# 3_SCHEMATIC_new.net
KiCad netlist of a schematic drawn in Altium Designer
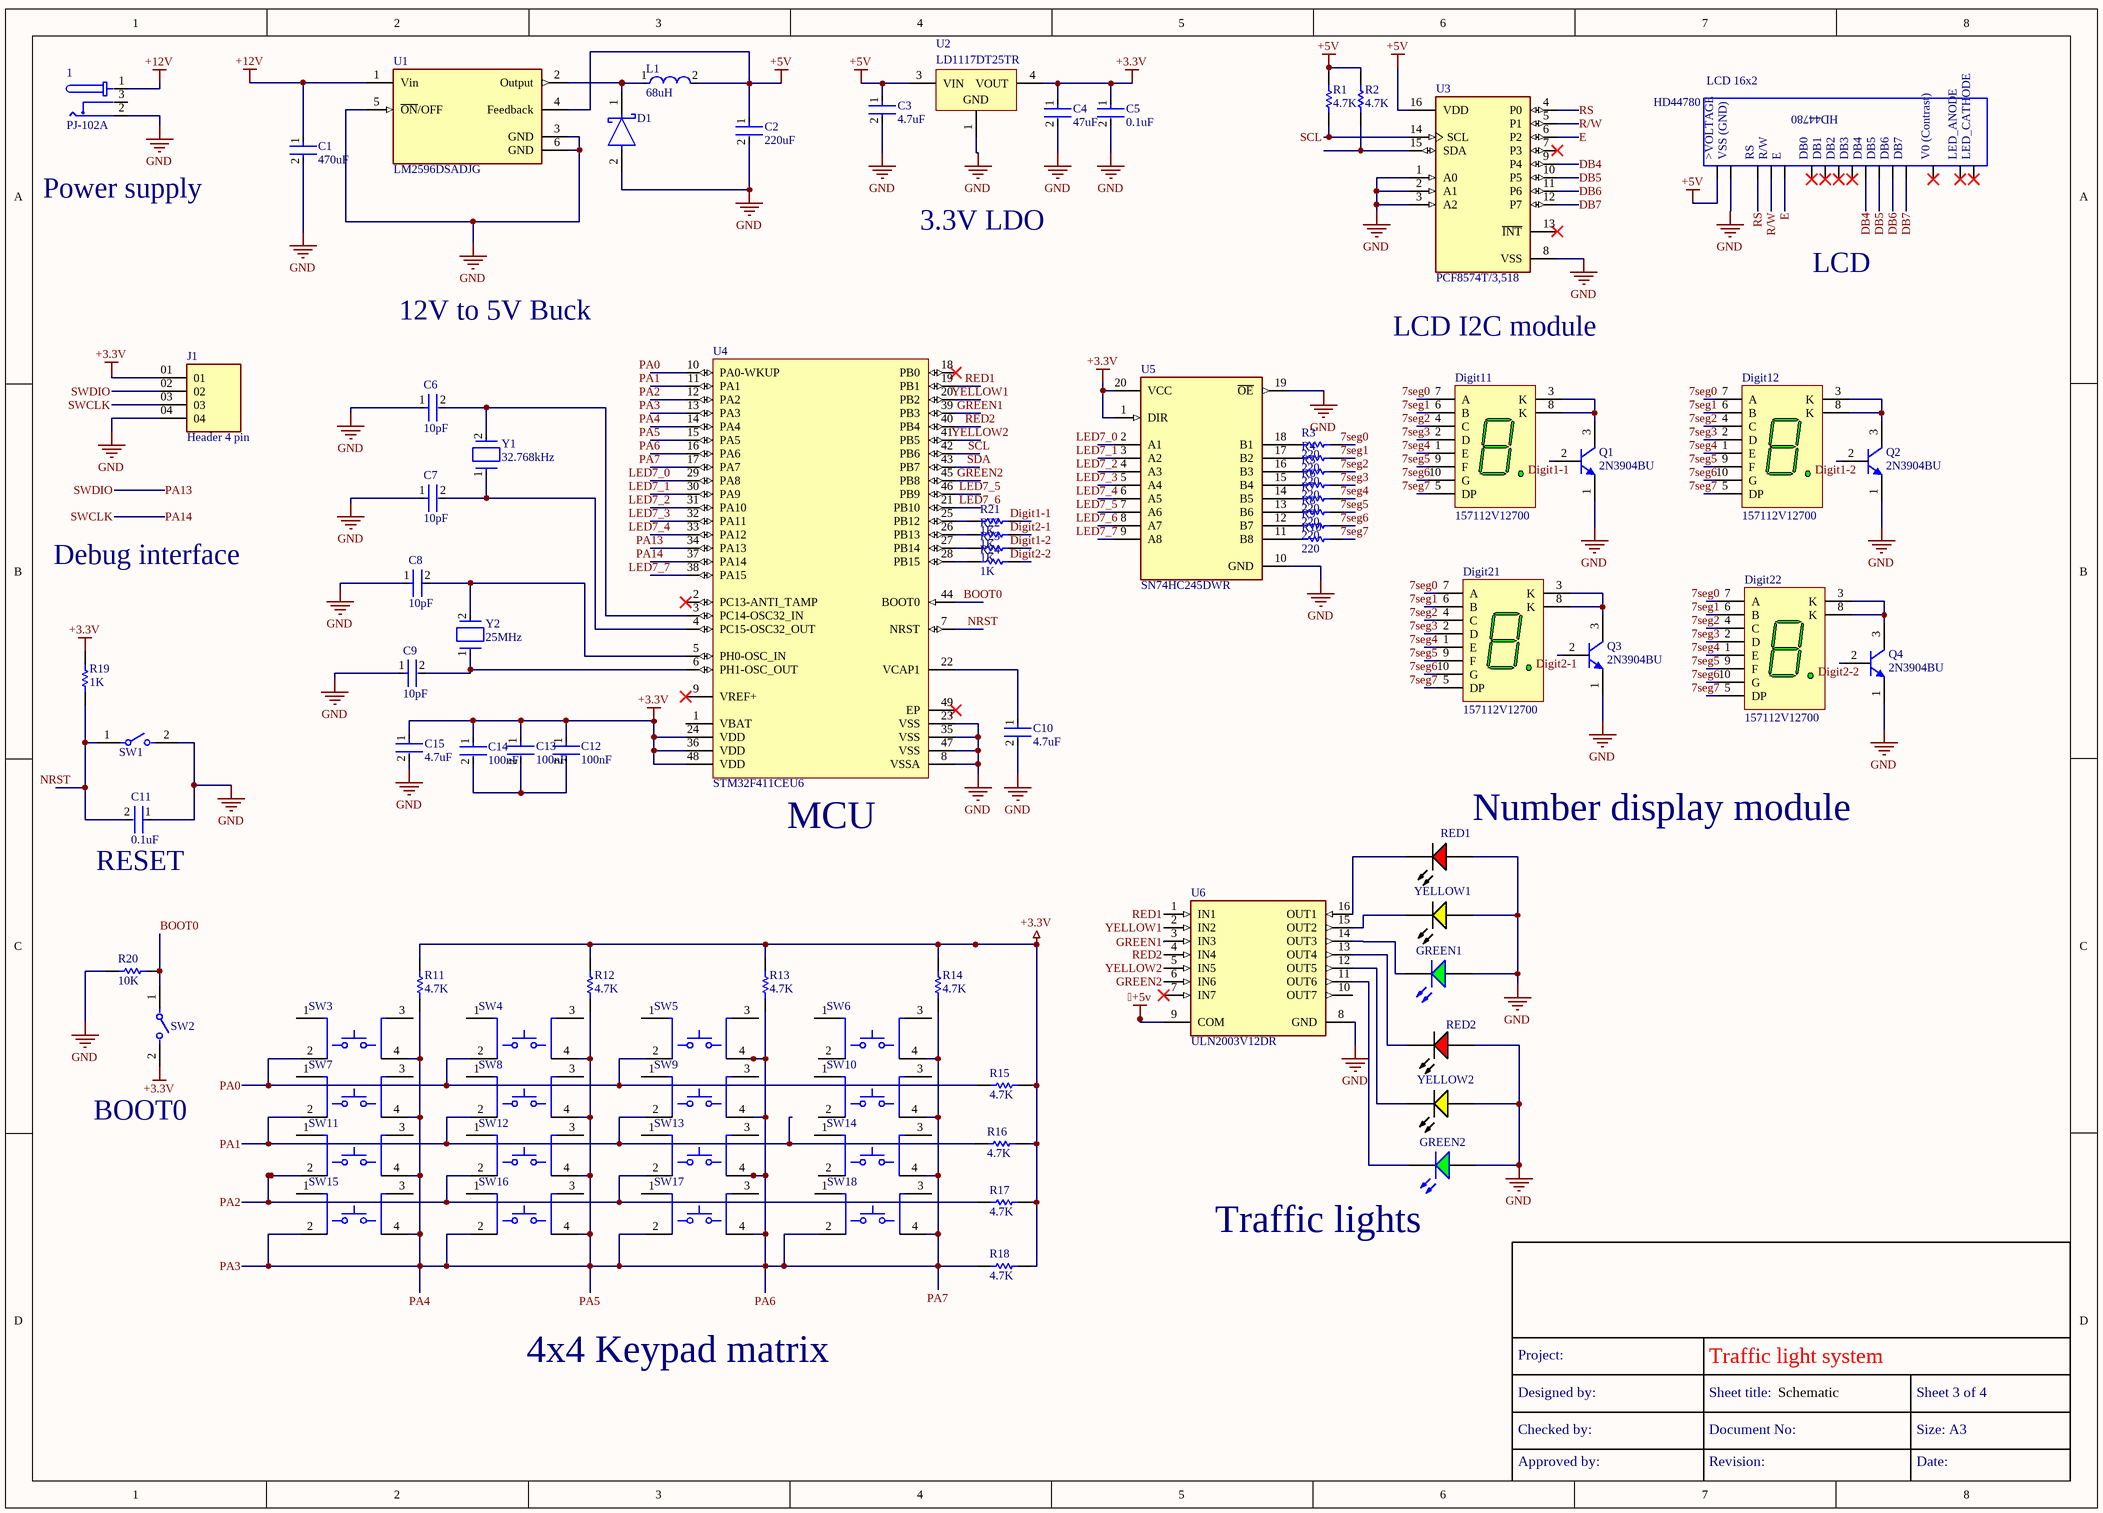
[diagram p0: [3] SCHEMATIC (new).SchDoc]

(export (version "E")
  (design (tool "Eeschema 10.0.6"))
  (components
    (comp (ref "1")
      (value "PJ-102A")
      (footprint "CUI_PJ-102A")
      (description "2.0 x 6.5 mm, 2.5 A, Horizontal, Through Hole, Tapered Pins, Dc Power Jack Connector")
      (fields (field (name "MF") "Same Sky"))
      (libsource (lib "PJ-102A") (part "PJ-102A"))
    )
    (comp (ref "C1")
      (value "470uF")
      (footprint "FP-1206-L_3_2_0_2-W_1_6_0-IPC_A")
      (description "None")
      (fields (field (name "TOLERANCE") "20%"))
      (libsource (lib "47uF capacitor") (part "CMP-14477-001040-2"))
    )
    (comp (ref "C2")
      (value "220uF")
      (footprint "FP-CC1210-GD-IPC_C")
      (description "CAP CER 220UF 6.3V X5R 1210")
      (fields (field (name "TOLERANCE") "20%"))
      (libsource (lib "220uF capacitor") (part "CMP-03422-001480-1"))
    )
    (comp (ref "C3")
      (value "4.7uF")
      (footprint "FP-1210-L_3_2_0_3-W_2_5_0-IPC_B")
      (description "None")
      (libsource (lib "4.7uF capacitor") (part "CMP-14477-002040-2"))
    )
    (comp (ref "C4")
      (value "47uF")
      (footprint "FP-1206-L_3_2_0_2-W_1_6_0-IPC_A")
      (description "None")
      (fields (field (name "TOLERANCE") "20%"))
      (libsource (lib "47uF capacitor") (part "CMP-14477-001040-2"))
    )
    (comp (ref "C5")
      (value "0.1uF")
      (footprint "FP-C1206C-EB-MFG")
      (description "C1206 0.10 μF U2J 2.00% 16 V")
      (fields
        (field (name "MANUFACTURER PART NUMBER") "C1206C104G4JACAUTO")
        (field (name "TOLERANCE") "0.02")
      )
      (libsource (lib "0.1uF capacitor") (part "CMP-03020-008411-1"))
    )
    (comp (ref "C6")
      (value "10pF")
      (footprint "FP-C0603C-CF-IPC_B")
      (description "C0603 10 pF X8R 30ppm/°C 5.00% 25 V")
      (fields
        (field (name "TOLERANCE") "0.05")
        (field (name "OCTOPART") "https://octopart.com/c0603c100j3hactu-kemet-88724797")
      )
      (libsource (lib "10pF capacitor") (part "CMP-03020-007367-1"))
    )
    (comp (ref "C7")
      (value "10pF")
      (footprint "FP-C0603C-CF-IPC_B")
      (description "C0603 10 pF X8R 30ppm/°C 5.00% 25 V")
      (fields
        (field (name "TOLERANCE") "0.05")
        (field (name "OCTOPART") "https://octopart.com/c0603c100j3hactu-kemet-88724797")
      )
      (libsource (lib "10pF capacitor") (part "CMP-03020-007367-1"))
    )
    (comp (ref "C8")
      (value "10pF")
      (footprint "FP-C0603C-CF-IPC_B")
      (description "C0603 10 pF X8R 30ppm/°C 5.00% 25 V")
      (fields
        (field (name "TOLERANCE") "0.05")
        (field (name "OCTOPART") "https://octopart.com/c0603c100j3hactu-kemet-88724797")
      )
      (libsource (lib "10pF capacitor") (part "CMP-03020-007367-1"))
    )
    (comp (ref "C9")
      (value "10pF")
      (footprint "FP-C0603C-CF-IPC_B")
      (description "C0603 10 pF X8R 30ppm/°C 5.00% 25 V")
      (fields
        (field (name "TOLERANCE") "0.05")
        (field (name "OCTOPART") "https://octopart.com/c0603c100j3hactu-kemet-88724797")
      )
      (libsource (lib "10pF capacitor") (part "CMP-03020-007367-1"))
    )
    (comp (ref "C10")
      (value "4.7uF")
      (footprint "FP-1210-L_3_2_0_3-W_2_5_0-IPC_B")
      (description "None")
      (libsource (lib "4.7uF capacitor") (part "CMP-14477-002040-2"))
    )
    (comp (ref "C11")
      (value "0.1uF")
      (footprint "FP-C1206C-EB-MFG")
      (description "C1206 0.10 μF U2J 2.00% 16 V")
      (fields
        (field (name "MANUFACTURER PART NUMBER") "C1206C104G4JACAUTO")
        (field (name "TOLERANCE") "0.02")
      )
      (libsource (lib "0.1uF capacitor") (part "CMP-03020-008411-1"))
    )
    (comp (ref "C12")
      (value "100nF")
      (footprint "FP-C1206C-EB-MFG")
      (description "C1206 0.10 μF U2J 2.00% 16 V")
      (fields
        (field (name "MANUFACTURER PART NUMBER") "C1206C104G4JACAUTO")
        (field (name "TOLERANCE") "0.02")
      )
      (libsource (lib "0.1uF capacitor") (part "CMP-03020-008411-1"))
    )
    (comp (ref "C13")
      (value "100nF")
      (footprint "FP-C1206C-EB-MFG")
      (description "C1206 0.10 μF U2J 2.00% 16 V")
      (fields
        (field (name "MANUFACTURER PART NUMBER") "C1206C104G4JACAUTO")
        (field (name "TOLERANCE") "0.02")
      )
      (libsource (lib "0.1uF capacitor") (part "CMP-03020-008411-1"))
    )
    (comp (ref "C14")
      (value "100nF")
      (footprint "FP-C1206C-EB-MFG")
      (description "C1206 0.10 μF U2J 2.00% 16 V")
      (fields
        (field (name "MANUFACTURER PART NUMBER") "C1206C104G4JACAUTO")
        (field (name "TOLERANCE") "0.02")
      )
      (libsource (lib "0.1uF capacitor") (part "CMP-03020-008411-1"))
    )
    (comp (ref "C15")
      (value "4.7uF")
      (footprint "FP-1210-L_3_2_0_3-W_2_5_0-IPC_B")
      (description "None")
      (libsource (lib "4.7uF capacitor") (part "CMP-14477-002040-2"))
    )
    (comp (ref "D1")
      (value "1N5818-T")
      (footprint "FP-DO-41_Plastic-MFG")
      (description "DIODE SCHOTTKY 30V 1A DO41")
      (fields
        (field (name "MANUFACTURER") "Diodes Inc.")
        (field (name "OCTOPART") "https://octopart.com/1n5818-t-diodes+inc.-55621749")
      )
      (libsource (lib "schottky diode") (part "CMP-12790-000035-1"))
    )
    (comp (ref "Digit11")
      (value "157112V12700")
      (footprint "WL-S7DS_L12W7.3H3.75")
      (description "7-Seg Display, Comm Cathode, Grn, 21Mcd Rohs Compliant: Yes ¦Wurth Elektronik 157112V12700")
      (libsource (lib "7 segment LED common cathode") (part "CMP-03913-119893988-3"))
    )
    (comp (ref "Digit12")
      (value "157112V12700")
      (footprint "WL-S7DS_L12W7.3H3.75")
      (description "7-Seg Display, Comm Cathode, Grn, 21Mcd Rohs Compliant: Yes ¦Wurth Elektronik 157112V12700")
      (libsource (lib "7 segment LED common cathode") (part "CMP-03913-119893988-3"))
    )
    (comp (ref "Digit21")
      (value "157112V12700")
      (footprint "WL-S7DS_L12W7.3H3.75")
      (description "7-Seg Display, Comm Cathode, Grn, 21Mcd Rohs Compliant: Yes ¦Wurth Elektronik 157112V12700")
      (libsource (lib "7 segment LED common cathode") (part "CMP-03913-119893988-3"))
    )
    (comp (ref "Digit22")
      (value "157112V12700")
      (footprint "WL-S7DS_L12W7.3H3.75")
      (description "7-Seg Display, Comm Cathode, Grn, 21Mcd Rohs Compliant: Yes ¦Wurth Elektronik 157112V12700")
      (libsource (lib "7 segment LED common cathode") (part "CMP-03913-119893988-3"))
    )
    (comp (ref "GREEN1")
      (value "WP7113SGD")
      (footprint "KING-WP7113SGD_V")
      (description "LED Green, 62.5 mW, 25 mA, -40 to 85 degC, 2-Pin THD, RoHS, Bulk")
      (fields (field (name "MANUFACTURER") "Kingbright"))
      (libsource (lib "green LED") (part "CMP-2100-03698-1"))
    )
    (comp (ref "GREEN2")
      (value "WP7113SGD")
      (footprint "KING-WP7113SGD_V")
      (description "LED Green, 62.5 mW, 25 mA, -40 to 85 degC, 2-Pin THD, RoHS, Bulk")
      (fields (field (name "MANUFACTURER") "Kingbright"))
      (libsource (lib "green LED") (part "CMP-2100-03698-1"))
    )
    (comp (ref "J1")
      (value "Header 4 pin")
      (footprint "SAMTEC_MTLW-104-X-X-S-X")
      (fields (field (name "MF") "{'manufacturer': u'Samtec Inc.'}") (field (name "MP") "MTLW-104-X-X-S-X"))
      (libsource (lib "MTLW-104-X-X-S-X") (part "MTLW-104-X-X-S-X"))
    )
    (comp (ref "L1")
      (value "68uH")
      (footprint "FP-LB2012-1_25-0_2-IPC_B")
      (description "SMD Inductors 68uH ±10% 0.05A 7.8Ω 0805")
      (fields (field (name "TOLERANCE") "10%"))
      (libsource (lib "inductor 68uH") (part "CMP-14484-000451-1"))
    )
    (comp (ref "LCD 16x2")
      (value "HD44780")
      (footprint "16026-16X2")
      (fields (field (name "MF") "Lumex Opto/Components"))
      (libsource (lib "HD44780") (part "HD44780"))
    )
    (comp (ref "Q1")
      (value "2N3904BU")
      (footprint "FAIR-TO-92")
      (description "NPN General-Purpose Amplifier, 40 V VCEO, 0.2 A, -55 to 150 degC, 2-Pin TO-92, RoHS, Bulk")
      (fields (field (name "MANUFACTURER") "FairchildSemiconductor"))
      (libsource (lib "npn 2n3904") (part "CMP-2000-04944-1"))
    )
    (comp (ref "Q2")
      (value "2N3904BU")
      (footprint "FAIR-TO-92")
      (description "NPN General-Purpose Amplifier, 40 V VCEO, 0.2 A, -55 to 150 degC, 2-Pin TO-92, RoHS, Bulk")
      (fields (field (name "MANUFACTURER") "FairchildSemiconductor"))
      (libsource (lib "npn 2n3904") (part "CMP-2000-04944-1"))
    )
    (comp (ref "Q3")
      (value "2N3904BU")
      (footprint "FAIR-TO-92")
      (description "NPN General-Purpose Amplifier, 40 V VCEO, 0.2 A, -55 to 150 degC, 2-Pin TO-92, RoHS, Bulk")
      (fields (field (name "MANUFACTURER") "FairchildSemiconductor"))
      (libsource (lib "npn 2n3904") (part "CMP-2000-04944-1"))
    )
    (comp (ref "Q4")
      (value "2N3904BU")
      (footprint "FAIR-TO-92")
      (description "NPN General-Purpose Amplifier, 40 V VCEO, 0.2 A, -55 to 150 degC, 2-Pin TO-92, RoHS, Bulk")
      (fields (field (name "MANUFACTURER") "FairchildSemiconductor"))
      (libsource (lib "npn 2n3904") (part "CMP-2000-04944-1"))
    )
    (comp (ref "R1")
      (value "4.7K")
      (footprint "RESC1005X40X25NL05T05")
      (fields (field (name "PART NUMBER") "CRCW04024K70JNTD") (field (name "MANUFACTURER") "Vishay Dale"))
      (libsource (lib "resistor 4.7k") (part "CMP-1011-00090-2"))
    )
    (comp (ref "R2")
      (value "4.7K")
      (footprint "RESC1005X40X25NL05T05")
      (fields (field (name "PART NUMBER") "CRCW04024K70JNTD") (field (name "MANUFACTURER") "Vishay Dale"))
      (libsource (lib "resistor 4.7k") (part "CMP-1011-00090-2"))
    )
    (comp (ref "R3")
      (value "220")
      (footprint "RESC3225X60X45ML20T20")
      (fields (field (name "MANUFACTURER") "Vishay Dale") (field (name "PART NUMBER") "CRCW1210220RJNEAHP"))
      (libsource (lib "resistor 220") (part "CMP-2005-00232-1"))
    )
    (comp (ref "R4")
      (value "220")
      (footprint "RESC3225X60X45ML20T20")
      (fields (field (name "MANUFACTURER") "Vishay Dale") (field (name "PART NUMBER") "CRCW1210220RJNEAHP"))
      (libsource (lib "resistor 220") (part "CMP-2005-00232-1"))
    )
    (comp (ref "R5")
      (value "220")
      (footprint "RESC3225X60X45ML20T20")
      (fields (field (name "MANUFACTURER") "Vishay Dale") (field (name "PART NUMBER") "CRCW1210220RJNEAHP"))
      (libsource (lib "resistor 220") (part "CMP-2005-00232-1"))
    )
    (comp (ref "R6")
      (value "220")
      (footprint "RESC3225X60X45ML20T20")
      (fields (field (name "MANUFACTURER") "Vishay Dale") (field (name "PART NUMBER") "CRCW1210220RJNEAHP"))
      (libsource (lib "resistor 220") (part "CMP-2005-00232-1"))
    )
    (comp (ref "R7")
      (value "220")
      (footprint "RESC3225X60X45ML20T20")
      (fields (field (name "MANUFACTURER") "Vishay Dale") (field (name "PART NUMBER") "CRCW1210220RJNEAHP"))
      (libsource (lib "resistor 220") (part "CMP-2005-00232-1"))
    )
    (comp (ref "R8")
      (value "220")
      (footprint "RESC3225X60X45ML20T20")
      (fields (field (name "MANUFACTURER") "Vishay Dale") (field (name "PART NUMBER") "CRCW1210220RJNEAHP"))
      (libsource (lib "resistor 220") (part "CMP-2005-00232-1"))
    )
    (comp (ref "R9")
      (value "220")
      (footprint "RESC3225X60X45ML20T20")
      (fields (field (name "MANUFACTURER") "Vishay Dale") (field (name "PART NUMBER") "CRCW1210220RJNEAHP"))
      (libsource (lib "resistor 220") (part "CMP-2005-00232-1"))
    )
    (comp (ref "R10")
      (value "220")
      (footprint "RESC3225X60X45ML20T20")
      (fields (field (name "MANUFACTURER") "Vishay Dale") (field (name "PART NUMBER") "CRCW1210220RJNEAHP"))
      (libsource (lib "resistor 220") (part "CMP-2005-00232-1"))
    )
    (comp (ref "R11")
      (value "4.7K")
      (footprint "RESC1005X40X25NL05T05")
      (fields (field (name "PART NUMBER") "CRCW04024K70JNTD") (field (name "MANUFACTURER") "Vishay Dale"))
      (libsource (lib "resistor 4.7k") (part "CMP-1011-00090-2"))
    )
    (comp (ref "R12")
      (value "4.7K")
      (footprint "RESC1005X40X25NL05T05")
      (fields (field (name "PART NUMBER") "CRCW04024K70JNTD") (field (name "MANUFACTURER") "Vishay Dale"))
      (libsource (lib "resistor 4.7k") (part "CMP-1011-00090-2"))
    )
    (comp (ref "R13")
      (value "4.7K")
      (footprint "RESC1005X40X25NL05T05")
      (fields (field (name "PART NUMBER") "CRCW04024K70JNTD") (field (name "MANUFACTURER") "Vishay Dale"))
      (libsource (lib "resistor 4.7k") (part "CMP-1011-00090-2"))
    )
    (comp (ref "R14")
      (value "4.7K")
      (footprint "RESC1005X40X25NL05T05")
      (fields (field (name "PART NUMBER") "CRCW04024K70JNTD") (field (name "MANUFACTURER") "Vishay Dale"))
      (libsource (lib "resistor 4.7k") (part "CMP-1011-00090-2"))
    )
    (comp (ref "R15")
      (value "4.7K")
      (footprint "RESC1005X40X25NL05T05")
      (fields (field (name "PART NUMBER") "CRCW04024K70JNTD") (field (name "MANUFACTURER") "Vishay Dale"))
      (libsource (lib "resistor 4.7k") (part "CMP-1011-00090-2"))
    )
    (comp (ref "R16")
      (value "4.7K")
      (footprint "RESC1005X40X25NL05T05")
      (fields (field (name "PART NUMBER") "CRCW04024K70JNTD") (field (name "MANUFACTURER") "Vishay Dale"))
      (libsource (lib "resistor 4.7k") (part "CMP-1011-00090-2"))
    )
    (comp (ref "R17")
      (value "4.7K")
      (footprint "RESC1005X40X25NL05T05")
      (fields (field (name "PART NUMBER") "CRCW04024K70JNTD") (field (name "MANUFACTURER") "Vishay Dale"))
      (libsource (lib "resistor 4.7k") (part "CMP-1011-00090-2"))
    )
    (comp (ref "R18")
      (value "4.7K")
      (footprint "RESC1005X40X25NL05T05")
      (fields (field (name "PART NUMBER") "CRCW04024K70JNTD") (field (name "MANUFACTURER") "Vishay Dale"))
      (libsource (lib "resistor 4.7k") (part "CMP-1011-00090-2"))
    )
    (comp (ref "R19")
      (value "1K")
      (footprint "RESC0603X28X15ML05T05")
      (fields (field (name "MANUFACTURER") "Vishay Dale") (field (name "PART NUMBER") "CRCW02011K00JNED"))
      (libsource (lib "resistor 1k") (part "CMP-1010-00074-2"))
    )
    (comp (ref "R20")
      (value "10K")
      (footprint "RESC2013X60X30NL20T20")
      (fields (field (name "MANUFACTURER") "KOA Speer") (field (name "PART NUMBER") "SG73S2ATTD1002F"))
      (libsource (lib "resistor 10K") (part "CMP-2001-02616-1"))
    )
    (comp (ref "R21")
      (value "1K")
      (footprint "RESC0603X28X15ML05T05")
      (fields (field (name "MANUFACTURER") "Vishay Dale") (field (name "PART NUMBER") "CRCW02011K00JNED"))
      (libsource (lib "resistor 1k") (part "CMP-1010-00074-2"))
    )
    (comp (ref "R22")
      (value "1K")
      (footprint "RESC0603X28X15ML05T05")
      (fields (field (name "MANUFACTURER") "Vishay Dale") (field (name "PART NUMBER") "CRCW02011K00JNED"))
      (libsource (lib "resistor 1k") (part "CMP-1010-00074-2"))
    )
    (comp (ref "R23")
      (value "1K")
      (footprint "RESC0603X28X15ML05T05")
      (fields (field (name "MANUFACTURER") "Vishay Dale") (field (name "PART NUMBER") "CRCW02011K00JNED"))
      (libsource (lib "resistor 1k") (part "CMP-1010-00074-2"))
    )
    (comp (ref "R24")
      (value "1K")
      (footprint "RESC0603X28X15ML05T05")
      (fields (field (name "MANUFACTURER") "Vishay Dale") (field (name "PART NUMBER") "CRCW02011K00JNED"))
      (libsource (lib "resistor 1k") (part "CMP-1010-00074-2"))
    )
    (comp (ref "RED1")
      (value "WP7113SRD/D")
      (footprint "KING-WP7113SRDD_V")
      (description "The Super Bright Red Source Color Device, 1.85 V, -40 to 85 degC, 2-Pin THD, RoHS, Tape and Reel")
      (libsource (lib "red LED") (part "CMP-1757-00002-1"))
    )
    (comp (ref "RED2")
      (value "WP7113SRD/D")
      (footprint "KING-WP7113SRDD_V")
      (description "The Super Bright Red Source Color Device, 1.85 V, -40 to 85 degC, 2-Pin THD, RoHS, Tape and Reel")
      (libsource (lib "red LED") (part "CMP-1757-00002-1"))
    )
    (comp (ref "SW1")
      (value "CHS-01TA")
      (footprint "FP-CHS-01TA-MFG")
      (description "SWITCH SLIDE DIP SPST 100MA 6V")
      (fields
        (field (name "OCTOPART") "https://octopart.com/chs-01ta-nidec+copal-52304644")
        (field (name "MANUFACTURER") "Nidec Copal Electronics")
      )
      (libsource (lib "switch") (part "CMP-71740-000003-1"))
    )
    (comp (ref "SW2")
      (value "CHS-01TA")
      (footprint "FP-CHS-01TA-MFG")
      (description "SWITCH SLIDE DIP SPST 100MA 6V")
      (fields
        (field (name "OCTOPART") "https://octopart.com/chs-01ta-nidec+copal-52304644")
        (field (name "MANUFACTURER") "Nidec Copal Electronics")
      )
      (libsource (lib "switch") (part "CMP-71740-000003-1"))
    )
    (comp (ref "SW3")
      (value "SKQBARA010")
      (footprint "FP-SKQBARA010-MFG")
      (description "SKQBARA010 Switch Tactile N.O. SPST Round Button PC Pins 0.05A 12VDC 1.57N Thru-Hole Automotive")
      (libsource (lib "push button") (part "CMP-00631-07849992-1"))
    )
    (comp (ref "SW4")
      (value "SKQBARA010")
      (footprint "FP-SKQBARA010-MFG")
      (description "SKQBARA010 Switch Tactile N.O. SPST Round Button PC Pins 0.05A 12VDC 1.57N Thru-Hole Automotive")
      (libsource (lib "push button") (part "CMP-00631-07849992-1"))
    )
    (comp (ref "SW5")
      (value "SKQBARA010")
      (footprint "FP-SKQBARA010-MFG")
      (description "SKQBARA010 Switch Tactile N.O. SPST Round Button PC Pins 0.05A 12VDC 1.57N Thru-Hole Automotive")
      (libsource (lib "push button") (part "CMP-00631-07849992-1"))
    )
    (comp (ref "SW6")
      (value "SKQBARA010")
      (footprint "FP-SKQBARA010-MFG")
      (description "SKQBARA010 Switch Tactile N.O. SPST Round Button PC Pins 0.05A 12VDC 1.57N Thru-Hole Automotive")
      (libsource (lib "push button") (part "CMP-00631-07849992-1"))
    )
    (comp (ref "SW7")
      (value "SKQBARA010")
      (footprint "FP-SKQBARA010-MFG")
      (description "SKQBARA010 Switch Tactile N.O. SPST Round Button PC Pins 0.05A 12VDC 1.57N Thru-Hole Automotive")
      (libsource (lib "push button") (part "CMP-00631-07849992-1"))
    )
    (comp (ref "SW8")
      (value "SKQBARA010")
      (footprint "FP-SKQBARA010-MFG")
      (description "SKQBARA010 Switch Tactile N.O. SPST Round Button PC Pins 0.05A 12VDC 1.57N Thru-Hole Automotive")
      (libsource (lib "push button") (part "CMP-00631-07849992-1"))
    )
    (comp (ref "SW9")
      (value "SKQBARA010")
      (footprint "FP-SKQBARA010-MFG")
      (description "SKQBARA010 Switch Tactile N.O. SPST Round Button PC Pins 0.05A 12VDC 1.57N Thru-Hole Automotive")
      (libsource (lib "push button") (part "CMP-00631-07849992-1"))
    )
    (comp (ref "SW10")
      (value "SKQBARA010")
      (footprint "FP-SKQBARA010-MFG")
      (description "SKQBARA010 Switch Tactile N.O. SPST Round Button PC Pins 0.05A 12VDC 1.57N Thru-Hole Automotive")
      (libsource (lib "push button") (part "CMP-00631-07849992-1"))
    )
    (comp (ref "SW11")
      (value "SKQBARA010")
      (footprint "FP-SKQBARA010-MFG")
      (description "SKQBARA010 Switch Tactile N.O. SPST Round Button PC Pins 0.05A 12VDC 1.57N Thru-Hole Automotive")
      (libsource (lib "push button") (part "CMP-00631-07849992-1"))
    )
    (comp (ref "SW12")
      (value "SKQBARA010")
      (footprint "FP-SKQBARA010-MFG")
      (description "SKQBARA010 Switch Tactile N.O. SPST Round Button PC Pins 0.05A 12VDC 1.57N Thru-Hole Automotive")
      (libsource (lib "push button") (part "CMP-00631-07849992-1"))
    )
    (comp (ref "SW13")
      (value "SKQBARA010")
      (footprint "FP-SKQBARA010-MFG")
      (description "SKQBARA010 Switch Tactile N.O. SPST Round Button PC Pins 0.05A 12VDC 1.57N Thru-Hole Automotive")
      (libsource (lib "push button") (part "CMP-00631-07849992-1"))
    )
    (comp (ref "SW14")
      (value "SKQBARA010")
      (footprint "FP-SKQBARA010-MFG")
      (description "SKQBARA010 Switch Tactile N.O. SPST Round Button PC Pins 0.05A 12VDC 1.57N Thru-Hole Automotive")
      (libsource (lib "push button") (part "CMP-00631-07849992-1"))
    )
    (comp (ref "SW15")
      (value "SKQBARA010")
      (footprint "FP-SKQBARA010-MFG")
      (description "SKQBARA010 Switch Tactile N.O. SPST Round Button PC Pins 0.05A 12VDC 1.57N Thru-Hole Automotive")
      (libsource (lib "push button") (part "CMP-00631-07849992-1"))
    )
    (comp (ref "SW16")
      (value "SKQBARA010")
      (footprint "FP-SKQBARA010-MFG")
      (description "SKQBARA010 Switch Tactile N.O. SPST Round Button PC Pins 0.05A 12VDC 1.57N Thru-Hole Automotive")
      (libsource (lib "push button") (part "CMP-00631-07849992-1"))
    )
    (comp (ref "SW17")
      (value "SKQBARA010")
      (footprint "FP-SKQBARA010-MFG")
      (description "SKQBARA010 Switch Tactile N.O. SPST Round Button PC Pins 0.05A 12VDC 1.57N Thru-Hole Automotive")
      (libsource (lib "push button") (part "CMP-00631-07849992-1"))
    )
    (comp (ref "SW18")
      (value "SKQBARA010")
      (footprint "FP-SKQBARA010-MFG")
      (description "SKQBARA010 Switch Tactile N.O. SPST Round Button PC Pins 0.05A 12VDC 1.57N Thru-Hole Automotive")
      (libsource (lib "push button") (part "CMP-00631-07849992-1"))
    )
    (comp (ref "U1")
      (value "LM2596DSADJG")
      (footprint "FP-936A-02-MFG")
      (description "IC REG MULT CONFG ADJ 3A D2PAK-5")
      (fields
        (field (name "OCTOPART") "https://octopart.com/lm2596dsadjg-on+semiconductor-12437034")
        (field (name "MANUFACTURER") "ON Semiconductor")
      )
      (libsource (lib "Components - 26.02.26 - 10.47") (part "CMP-07129-000001-1"))
    )
    (comp (ref "U2")
      (value "LD1117DT25TR")
      (footprint "TO-252_L")
      (description "Fixed Low Drop Positive Voltage Regulator, 3-Pin DPAK, Tape and Reel")
      (libsource (lib "LD1117") (part "CMP-0244-00090-1"))
    )
    (comp (ref "U3")
      (value "PCF8574T/3,518")
      (footprint "FP-SOT162-1-MFG")
      (description "IC I/O EXPANDER I2C 8B 16SOIC")
      (fields
        (field (name "MANUFACTURER") "NXP Semiconductors")
        (field (name "OCTOPART") "https://octopart.com/pcf8574t%2F3%2C518-nxp+semiconductors-10470852")
      )
      (libsource (lib "Components - 02.03.26 - 13.28") (part "CMP-10112-000010-1"))
    )
    (comp (ref "U4")
      (value "STM32F411CEU6")
      (footprint "STM-UFQFPN48_L")
      (libsource (lib "Altium Content Vault") (part "MC-ARM-STM32F411-UFQFPN48"))
    )
    (comp (ref "U5")
      (value "SN74HC245DWR")
      (footprint "FP-DW0020A-MFG")
      (description "IC TRANSCVR NON-INVERT 6V 20SOIC")
      (libsource (lib "74hc245") (part "CMP-1620-00193-3"))
    )
    (comp (ref "U6")
      (value "ULN2003V12DR")
      (footprint "FP-D0016A-MFG")
      (description "MOSFET 7CH 16SOIC")
      (libsource (lib "ULN2003") (part "CMP-04912-000075-1"))
    )
    (comp (ref "Y1")
      (value "32.768kHz")
      (footprint "FP-ABS09-MFG")
      (description "CRYSTAL 32.7680KHZ 12.5PF SMD")
      (fields (field (name "TOLERANCE") "10ppm"))
      (libsource (lib "crystal 32.768khz") (part "CMP-27762-005385-1"))
    )
    (comp (ref "Y2")
      (value "25MHz")
      (footprint "FP-7A-MFG")
      (description "Quartz Crystal 25MHz, 30ppm, 12pF, 50Ω")
      (libsource (lib "crystal 25mhz") (part "CMP-18717-000353-1"))
    )
    (comp (ref "YELLOW1")
      (value "WP7113SYD")
      (footprint "KING-WP7113SYD_V")
      (description "The Super Bright Yellow Device, 2 V, -40 to 85 degC, 2-Pin THD, RoHS, Tape and Reel")
      (fields (field (name "TOLERANCE") "1%"))
      (libsource (lib "yellow LED") (part "CMP-1757-00003-1"))
    )
    (comp (ref "YELLOW2")
      (value "WP7113SYD")
      (footprint "KING-WP7113SYD_V")
      (description "The Super Bright Yellow Device, 2 V, -40 to 85 degC, 2-Pin THD, RoHS, Tape and Reel")
      (fields (field (name "TOLERANCE") "1%"))
      (libsource (lib "yellow LED") (part "CMP-1757-00003-1"))
    )
  )
  (nets
    (net (code "1") (name "+5V") (class "Default")
      (node (ref "C2") (pin "1") (pinfunction "1_1") (pintype "passive"))
      (node (ref "C3") (pin "1") (pinfunction "1_1") (pintype "passive"))
      (node (ref "L1") (pin "2") (pinfunction "2_2") (pintype "passive"))
      (node (ref "LCD 16x2") (pin "P$2") (pinfunction "VDD_P$2") (pintype "power_in"))
      (node (ref "R1") (pin "2") (pinfunction "2_2") (pintype "passive"))
      (node (ref "R2") (pin "2") (pinfunction "2_2") (pintype "passive"))
      (node (ref "U1") (pin "4") (pinfunction "Feedback_4") (pintype "passive"))
      (node (ref "U2") (pin "3") (pinfunction "VIN_3") (pintype "power_in"))
      (node (ref "U3") (pin "16") (pinfunction "VDD_16") (pintype "power_in"))
    )
    (net (code "2") (name "+12V") (class "Default")
      (node (ref "1") (pin "1") (pinfunction "1_1") (pintype "power_in"))
      (node (ref "C1") (pin "1") (pinfunction "1_1") (pintype "passive"))
      (node (ref "U1") (pin "1") (pinfunction "Vin_1") (pintype "power_in"))
    )
    (net (code "3") (name "/7seg0") (class "Default")
      (node (ref "Digit11") (pin "7") (pinfunction "A_7") (pintype "passive"))
      (node (ref "Digit12") (pin "7") (pinfunction "A_7") (pintype "passive"))
      (node (ref "Digit21") (pin "7") (pinfunction "A_7") (pintype "passive"))
      (node (ref "Digit22") (pin "7") (pinfunction "A_7") (pintype "passive"))
      (node (ref "R3") (pin "2") (pinfunction "2_2") (pintype "passive"))
    )
    (net (code "4") (name "/7seg1") (class "Default")
      (node (ref "Digit11") (pin "6") (pinfunction "B_6") (pintype "passive"))
      (node (ref "Digit12") (pin "6") (pinfunction "B_6") (pintype "passive"))
      (node (ref "Digit21") (pin "6") (pinfunction "B_6") (pintype "passive"))
      (node (ref "Digit22") (pin "6") (pinfunction "B_6") (pintype "passive"))
      (node (ref "R4") (pin "2") (pinfunction "2_2") (pintype "passive"))
    )
    (net (code "5") (name "/7seg2") (class "Default")
      (node (ref "Digit11") (pin "4") (pinfunction "C_4") (pintype "passive"))
      (node (ref "Digit12") (pin "4") (pinfunction "C_4") (pintype "passive"))
      (node (ref "Digit21") (pin "4") (pinfunction "C_4") (pintype "passive"))
      (node (ref "Digit22") (pin "4") (pinfunction "C_4") (pintype "passive"))
      (node (ref "R5") (pin "2") (pinfunction "2_2") (pintype "passive"))
    )
    (net (code "6") (name "/7seg3") (class "Default")
      (node (ref "Digit11") (pin "2") (pinfunction "D_2") (pintype "passive"))
      (node (ref "Digit12") (pin "2") (pinfunction "D_2") (pintype "passive"))
      (node (ref "Digit21") (pin "2") (pinfunction "D_2") (pintype "passive"))
      (node (ref "Digit22") (pin "2") (pinfunction "D_2") (pintype "passive"))
      (node (ref "R6") (pin "2") (pinfunction "2_2") (pintype "passive"))
    )
    (net (code "7") (name "/7seg4") (class "Default")
      (node (ref "Digit11") (pin "1") (pinfunction "E_1") (pintype "passive"))
      (node (ref "Digit12") (pin "1") (pinfunction "E_1") (pintype "passive"))
      (node (ref "Digit21") (pin "1") (pinfunction "E_1") (pintype "passive"))
      (node (ref "Digit22") (pin "1") (pinfunction "E_1") (pintype "passive"))
      (node (ref "R7") (pin "2") (pinfunction "2_2") (pintype "passive"))
    )
    (net (code "8") (name "/7seg5") (class "Default")
      (node (ref "Digit11") (pin "9") (pinfunction "F_9") (pintype "passive"))
      (node (ref "Digit12") (pin "9") (pinfunction "F_9") (pintype "passive"))
      (node (ref "Digit21") (pin "9") (pinfunction "F_9") (pintype "passive"))
      (node (ref "Digit22") (pin "9") (pinfunction "F_9") (pintype "passive"))
      (node (ref "R8") (pin "2") (pinfunction "2_2") (pintype "passive"))
    )
    (net (code "9") (name "/7seg6") (class "Default")
      (node (ref "Digit11") (pin "10") (pinfunction "G_10") (pintype "passive"))
      (node (ref "Digit12") (pin "10") (pinfunction "G_10") (pintype "passive"))
      (node (ref "Digit21") (pin "10") (pinfunction "G_10") (pintype "passive"))
      (node (ref "Digit22") (pin "10") (pinfunction "G_10") (pintype "passive"))
      (node (ref "R9") (pin "2") (pinfunction "2_2") (pintype "passive"))
    )
    (net (code "10") (name "/7seg7") (class "Default")
      (node (ref "Digit11") (pin "5") (pinfunction "DP_5") (pintype "passive"))
      (node (ref "Digit12") (pin "5") (pinfunction "DP_5") (pintype "passive"))
      (node (ref "Digit21") (pin "5") (pinfunction "DP_5") (pintype "passive"))
      (node (ref "Digit22") (pin "5") (pinfunction "DP_5") (pintype "passive"))
      (node (ref "R10") (pin "2") (pinfunction "2_2") (pintype "passive"))
    )
    (net (code "11") (name "/BOOT0") (class "Default")
      (node (ref "R20") (pin "2") (pinfunction "2_2") (pintype "passive"))
      (node (ref "SW2") (pin "1") (pinfunction "1_1") (pintype "passive"))
      (node (ref "U4") (pin "44") (pinfunction "BOOT0_44") (pintype "input"))
    )
    (net (code "12") (name "/DB4") (class "Default")
      (node (ref "LCD 16x2") (pin "P$11") (pinfunction "DB4_P$11") (pintype "bidirectional"))
      (node (ref "U3") (pin "9") (pinfunction "P4_9") (pintype "bidirectional"))
    )
    (net (code "13") (name "/DB5") (class "Default")
      (node (ref "LCD 16x2") (pin "P$12") (pinfunction "DB5_P$12") (pintype "bidirectional"))
      (node (ref "U3") (pin "10") (pinfunction "P5_10") (pintype "bidirectional"))
    )
    (net (code "14") (name "/DB6") (class "Default")
      (node (ref "LCD 16x2") (pin "P$13") (pinfunction "DB6_P$13") (pintype "bidirectional"))
      (node (ref "U3") (pin "11") (pinfunction "P6_11") (pintype "bidirectional"))
    )
    (net (code "15") (name "/DB7") (class "Default")
      (node (ref "LCD 16x2") (pin "P$14") (pinfunction "DB7_P$14") (pintype "bidirectional"))
      (node (ref "U3") (pin "12") (pinfunction "P7_12") (pintype "bidirectional"))
    )
    (net (code "16") (name "/Digit1-1") (class "Default")
      (node (ref "Q1") (pin "2") (pinfunction "B_2") (pintype "passive"))
      (node (ref "R21") (pin "2") (pinfunction "2_2") (pintype "passive"))
    )
    (net (code "17") (name "/Digit1-2") (class "Default")
      (node (ref "Q2") (pin "2") (pinfunction "B_2") (pintype "passive"))
      (node (ref "R23") (pin "2") (pinfunction "2_2") (pintype "passive"))
    )
    (net (code "18") (name "/Digit2-1") (class "Default")
      (node (ref "Q3") (pin "2") (pinfunction "B_2") (pintype "passive"))
      (node (ref "R22") (pin "2") (pinfunction "2_2") (pintype "passive"))
    )
    (net (code "19") (name "/Digit2-2") (class "Default")
      (node (ref "Q4") (pin "2") (pinfunction "B_2") (pintype "passive"))
      (node (ref "R24") (pin "2") (pinfunction "2_2") (pintype "passive"))
    )
    (net (code "20") (name "/E") (class "Default")
      (node (ref "LCD 16x2") (pin "P$6") (pinfunction "E_P$6") (pintype "bidirectional"))
      (node (ref "U3") (pin "6") (pinfunction "P2_6") (pintype "bidirectional"))
    )
    (net (code "21") (name "/GREEN1") (class "Default")
      (node (ref "U4") (pin "39") (pinfunction "PB3_39") (pintype "bidirectional"))
      (node (ref "U6") (pin "3") (pinfunction "IN3_3") (pintype "input"))
    )
    (net (code "22") (name "/GREEN2") (class "Default")
      (node (ref "U4") (pin "45") (pinfunction "PB8_45") (pintype "bidirectional"))
      (node (ref "U6") (pin "6") (pinfunction "IN6_6") (pintype "input"))
    )
    (net (code "23") (name "/LED7_0") (class "Default")
      (node (ref "U4") (pin "29") (pinfunction "PA8_29") (pintype "bidirectional"))
      (node (ref "U5") (pin "2") (pinfunction "A1_2") (pintype "passive"))
    )
    (net (code "24") (name "/LED7_1") (class "Default")
      (node (ref "U4") (pin "30") (pinfunction "PA9_30") (pintype "bidirectional"))
      (node (ref "U5") (pin "3") (pinfunction "A2_3") (pintype "passive"))
    )
    (net (code "25") (name "/LED7_2") (class "Default")
      (node (ref "U4") (pin "31") (pinfunction "PA10_31") (pintype "bidirectional"))
      (node (ref "U5") (pin "4") (pinfunction "A3_4") (pintype "passive"))
    )
    (net (code "26") (name "/LED7_3") (class "Default")
      (node (ref "U4") (pin "32") (pinfunction "PA11_32") (pintype "bidirectional"))
      (node (ref "U5") (pin "5") (pinfunction "A4_5") (pintype "passive"))
    )
    (net (code "27") (name "/LED7_4") (class "Default")
      (node (ref "U4") (pin "33") (pinfunction "PA12_33") (pintype "bidirectional"))
      (node (ref "U5") (pin "6") (pinfunction "A5_6") (pintype "passive"))
    )
    (net (code "28") (name "/LED7_5") (class "Default")
      (node (ref "U4") (pin "46") (pinfunction "PB9_46") (pintype "bidirectional"))
      (node (ref "U5") (pin "7") (pinfunction "A6_7") (pintype "passive"))
    )
    (net (code "29") (name "/LED7_6") (class "Default")
      (node (ref "U4") (pin "21") (pinfunction "PB10_21") (pintype "bidirectional"))
      (node (ref "U5") (pin "8") (pinfunction "A7_8") (pintype "passive"))
    )
    (net (code "30") (name "/LED7_7") (class "Default")
      (node (ref "U4") (pin "38") (pinfunction "PA15_38") (pintype "bidirectional"))
      (node (ref "U5") (pin "9") (pinfunction "A8_9") (pintype "passive"))
    )
    (net (code "31") (name "/NRST") (class "Default")
      (node (ref "C11") (pin "2") (pinfunction "2_2") (pintype "passive"))
      (node (ref "R19") (pin "1") (pinfunction "1_1") (pintype "passive"))
      (node (ref "SW1") (pin "1") (pinfunction "1_1") (pintype "passive"))
      (node (ref "U4") (pin "7") (pinfunction "NRST_7") (pintype "bidirectional"))
    )
    (net (code "32") (name "/PA0") (class "Default")
      (node (ref "R15") (pin "2") (pinfunction "2_2") (pintype "passive"))
      (node (ref "SW3") (pin "2") (pinfunction "2_2") (pintype "passive"))
      (node (ref "SW4") (pin "2") (pinfunction "2_2") (pintype "passive"))
      (node (ref "SW5") (pin "2") (pinfunction "2_2") (pintype "passive"))
      (node (ref "U4") (pin "10") (pinfunction "PA0-WKUP_10") (pintype "bidirectional"))
    )
    (net (code "33") (name "/PA1") (class "Default")
      (node (ref "R16") (pin "2") (pinfunction "2_2") (pintype "passive"))
      (node (ref "SW7") (pin "2") (pinfunction "2_2") (pintype "passive"))
      (node (ref "SW8") (pin "2") (pinfunction "2_2") (pintype "passive"))
      (node (ref "SW9") (pin "2") (pinfunction "2_2") (pintype "passive"))
      (node (ref "U4") (pin "11") (pinfunction "PA1_11") (pintype "bidirectional"))
    )
    (net (code "34") (name "/PA2") (class "Default")
      (node (ref "R17") (pin "2") (pinfunction "2_2") (pintype "passive"))
      (node (ref "SW11") (pin "2") (pinfunction "2_2") (pintype "passive"))
      (node (ref "SW12") (pin "2") (pinfunction "2_2") (pintype "passive"))
      (node (ref "SW13") (pin "2") (pinfunction "2_2") (pintype "passive"))
      (node (ref "U4") (pin "12") (pinfunction "PA2_12") (pintype "bidirectional"))
    )
    (net (code "35") (name "/PA3") (class "Default")
      (node (ref "R11") (pin "1") (pinfunction "1_1") (pintype "passive"))
      (node (ref "R12") (pin "1") (pinfunction "1_1") (pintype "passive"))
      (node (ref "R13") (pin "1") (pinfunction "1_1") (pintype "passive"))
      (node (ref "R14") (pin "1") (pinfunction "1_1") (pintype "passive"))
      (node (ref "R18") (pin "2") (pinfunction "2_2") (pintype "passive"))
      (node (ref "SW10") (pin "4") (pinfunction "4_4") (pintype "passive"))
      (node (ref "SW11") (pin "4") (pinfunction "4_4") (pintype "passive"))
      (node (ref "SW12") (pin "4") (pinfunction "4_4") (pintype "passive"))
      (node (ref "SW13") (pin "4") (pinfunction "4_4") (pintype "passive"))
      (node (ref "SW14") (pin "4") (pinfunction "4_4") (pintype "passive"))
      (node (ref "SW15") (pin "2") (pinfunction "2_2") (pintype "passive"))
      (node (ref "SW15") (pin "4") (pinfunction "4_4") (pintype "passive"))
      (node (ref "SW16") (pin "2") (pinfunction "2_2") (pintype "passive"))
      (node (ref "SW16") (pin "4") (pinfunction "4_4") (pintype "passive"))
      (node (ref "SW17") (pin "2") (pinfunction "2_2") (pintype "passive"))
      (node (ref "SW17") (pin "4") (pinfunction "4_4") (pintype "passive"))
      (node (ref "SW18") (pin "2") (pinfunction "2_2") (pintype "passive"))
      (node (ref "SW18") (pin "4") (pinfunction "4_4") (pintype "passive"))
      (node (ref "SW3") (pin "4") (pinfunction "4_4") (pintype "passive"))
      (node (ref "SW4") (pin "4") (pinfunction "4_4") (pintype "passive"))
      (node (ref "SW5") (pin "4") (pinfunction "4_4") (pintype "passive"))
      (node (ref "SW6") (pin "4") (pinfunction "4_4") (pintype "passive"))
      (node (ref "SW7") (pin "4") (pinfunction "4_4") (pintype "passive"))
      (node (ref "SW8") (pin "4") (pinfunction "4_4") (pintype "passive"))
      (node (ref "SW9") (pin "4") (pinfunction "4_4") (pintype "passive"))
      (node (ref "U4") (pin "13") (pinfunction "PA3_13") (pintype "bidirectional"))
      (node (ref "U4") (pin "14") (pinfunction "PA4_14") (pintype "bidirectional"))
      (node (ref "U4") (pin "15") (pinfunction "PA5_15") (pintype "bidirectional"))
      (node (ref "U4") (pin "16") (pinfunction "PA6_16") (pintype "bidirectional"))
      (node (ref "U4") (pin "17") (pinfunction "PA7_17") (pintype "bidirectional"))
    )
    (net (code "36") (name "/PA13") (class "Default")
      (node (ref "J1") (pin "02") (pinfunction "02_02") (pintype "passive"))
      (node (ref "U4") (pin "34") (pinfunction "PA13_34") (pintype "bidirectional"))
    )
    (net (code "37") (name "/PA14") (class "Default")
      (node (ref "J1") (pin "03") (pinfunction "03_03") (pintype "passive"))
      (node (ref "U4") (pin "37") (pinfunction "PA14_37") (pintype "bidirectional"))
    )
    (net (code "38") (name "/RED1") (class "Default")
      (node (ref "U4") (pin "19") (pinfunction "PB1_19") (pintype "bidirectional"))
      (node (ref "U6") (pin "1") (pinfunction "IN1_1") (pintype "input"))
    )
    (net (code "39") (name "/RED2") (class "Default")
      (node (ref "U4") (pin "40") (pinfunction "PB4_40") (pintype "bidirectional"))
      (node (ref "U6") (pin "4") (pinfunction "IN4_4") (pintype "input"))
    )
    (net (code "40") (name "/RS") (class "Default")
      (node (ref "LCD 16x2") (pin "P$4") (pinfunction "RS_P$4") (pintype "bidirectional"))
      (node (ref "U3") (pin "4") (pinfunction "P0_4") (pintype "bidirectional"))
    )
    (net (code "41") (name "/R{slash}W") (class "Default")
      (node (ref "LCD 16x2") (pin "P$5") (pinfunction "R/W_P$5") (pintype "bidirectional"))
      (node (ref "U3") (pin "5") (pinfunction "P1_5") (pintype "bidirectional"))
    )
    (net (code "42") (name "/SCL") (class "Default")
      (node (ref "R1") (pin "1") (pinfunction "1_1") (pintype "passive"))
      (node (ref "U3") (pin "14") (pinfunction "SCL_14") (pintype "input"))
      (node (ref "U4") (pin "42") (pinfunction "PB6_42") (pintype "bidirectional"))
    )
    (net (code "43") (name "/SDA") (class "Default")
      (node (ref "U4") (pin "43") (pinfunction "PB7_43") (pintype "bidirectional"))
    )
    (net (code "44") (name "/YELLOW1") (class "Default")
      (node (ref "U4") (pin "20") (pinfunction "PB2_20") (pintype "bidirectional"))
      (node (ref "U6") (pin "2") (pinfunction "IN2_2") (pintype "input"))
    )
    (net (code "45") (name "/YELLOW2") (class "Default")
      (node (ref "U4") (pin "41") (pinfunction "PB5_41") (pintype "bidirectional"))
      (node (ref "U6") (pin "5") (pinfunction "IN5_5") (pintype "input"))
    )
    (net (code "46") (name "<NO NET>") (class "Default")
      (node (ref "C12") (pin "1") (pinfunction "1_1") (pintype "passive"))
      (node (ref "C13") (pin "1") (pinfunction "1_1") (pintype "passive"))
      (node (ref "C14") (pin "1") (pinfunction "1_1") (pintype "passive"))
      (node (ref "C15") (pin "1") (pinfunction "1_1") (pintype "passive"))
      (node (ref "C4") (pin "1") (pinfunction "1_1") (pintype "passive"))
      (node (ref "C5") (pin "1") (pinfunction "1_1") (pintype "passive"))
      (node (ref "J1") (pin "01") (pinfunction "01_01") (pintype "passive"))
      (node (ref "R11") (pin "2") (pinfunction "2_2") (pintype "passive"))
      (node (ref "R12") (pin "2") (pinfunction "2_2") (pintype "passive"))
      (node (ref "R13") (pin "2") (pinfunction "2_2") (pintype "passive"))
      (node (ref "R14") (pin "2") (pinfunction "2_2") (pintype "passive"))
      (node (ref "R15") (pin "1") (pinfunction "1_1") (pintype "passive"))
      (node (ref "R16") (pin "1") (pinfunction "1_1") (pintype "passive"))
      (node (ref "R17") (pin "1") (pinfunction "1_1") (pintype "passive"))
      (node (ref "R18") (pin "1") (pinfunction "1_1") (pintype "passive"))
      (node (ref "R19") (pin "2") (pinfunction "2_2") (pintype "passive"))
      (node (ref "SW2") (pin "2") (pinfunction "2_2") (pintype "passive"))
      (node (ref "U2") (pin "4") (pinfunction "VOUT_4") (pintype "power_in"))
      (node (ref "U4") (pin "24") (pinfunction "VDD_24") (pintype "power_in"))
      (node (ref "U4") (pin "36") (pinfunction "VDD_36") (pintype "power_in"))
      (node (ref "U4") (pin "48") (pinfunction "VDD_48") (pintype "power_in"))
      (node (ref "U5") (pin "1") (pinfunction "DIR_1") (pintype "input"))
      (node (ref "U5") (pin "20") (pinfunction "VCC_20") (pintype "open_emitter"))
      (node (ref "U6") (pin "9") (pinfunction "COM_9") (pintype "passive"))
    )
    (net (code "47") (name "GND") (class "Default")
      (node (ref "1") (pin "2") (pinfunction "2_2") (pintype "power_in"))
      (node (ref "C1") (pin "2") (pinfunction "2_2") (pintype "passive"))
      (node (ref "C10") (pin "2") (pinfunction "2_2") (pintype "passive"))
      (node (ref "C11") (pin "1") (pinfunction "1_1") (pintype "passive"))
      (node (ref "C15") (pin "2") (pinfunction "2_2") (pintype "passive"))
      (node (ref "C2") (pin "2") (pinfunction "2_2") (pintype "passive"))
      (node (ref "C3") (pin "2") (pinfunction "2_2") (pintype "passive"))
      (node (ref "C4") (pin "2") (pinfunction "2_2") (pintype "passive"))
      (node (ref "C5") (pin "2") (pinfunction "2_2") (pintype "passive"))
      (node (ref "C6") (pin "1") (pinfunction "1_1") (pintype "passive"))
      (node (ref "C7") (pin "1") (pinfunction "1_1") (pintype "passive"))
      (node (ref "C8") (pin "1") (pinfunction "1_1") (pintype "passive"))
      (node (ref "C9") (pin "1") (pinfunction "1_1") (pintype "passive"))
      (node (ref "D1") (pin "2") (pinfunction "A_2") (pintype "passive"))
      (node (ref "GREEN1") (pin "1") (pinfunction "A_1") (pintype "passive"))
      (node (ref "GREEN2") (pin "1") (pinfunction "A_1") (pintype "passive"))
      (node (ref "J1") (pin "04") (pinfunction "04_04") (pintype "passive"))
      (node (ref "LCD 16x2") (pin "P$1") (pinfunction "VSS_P$1") (pintype "power_in"))
      (node (ref "Q1") (pin "1") (pinfunction "E_1") (pintype "passive"))
      (node (ref "Q2") (pin "1") (pinfunction "E_1") (pintype "passive"))
      (node (ref "Q3") (pin "1") (pinfunction "E_1") (pintype "passive"))
      (node (ref "Q4") (pin "1") (pinfunction "E_1") (pintype "passive"))
      (node (ref "R20") (pin "1") (pinfunction "1_1") (pintype "passive"))
      (node (ref "RED1") (pin "1") (pinfunction "A_1") (pintype "passive"))
      (node (ref "RED2") (pin "1") (pinfunction "A_1") (pintype "passive"))
      (node (ref "SW1") (pin "2") (pinfunction "2_2") (pintype "passive"))
      (node (ref "U1") (pin "3") (pinfunction "GND_3") (pintype "power_in"))
      (node (ref "U1") (pin "5") (pinfunction "~{ON}/OFF_5") (pintype "input"))
      (node (ref "U1") (pin "6") (pinfunction "GND_6") (pintype "power_in"))
      (node (ref "U2") (pin "1") (pinfunction "GND_1") (pintype "power_in"))
      (node (ref "U3") (pin "1") (pinfunction "A0_1") (pintype "input"))
      (node (ref "U3") (pin "2") (pinfunction "A1_2") (pintype "input"))
      (node (ref "U3") (pin "3") (pinfunction "A2_3") (pintype "input"))
      (node (ref "U3") (pin "8") (pinfunction "VSS_8") (pintype "power_in"))
      (node (ref "U4") (pin "23") (pinfunction "VSS_23") (pintype "power_in"))
      (node (ref "U4") (pin "35") (pinfunction "VSS_35") (pintype "power_in"))
      (node (ref "U4") (pin "47") (pinfunction "VSS_47") (pintype "power_in"))
      (node (ref "U4") (pin "8") (pinfunction "VSSA_8") (pintype "power_in"))
      (node (ref "U5") (pin "10") (pinfunction "GND_10") (pintype "power_in"))
      (node (ref "U5") (pin "19") (pinfunction "~{OE}_19") (pintype "output"))
      (node (ref "U6") (pin "8") (pinfunction "GND_8") (pintype "power_in"))
      (node (ref "YELLOW1") (pin "1") (pinfunction "A_1") (pintype "passive"))
      (node (ref "YELLOW2") (pin "1") (pinfunction "A_1") (pintype "passive"))
    )
    (net (code "48") (name "Net-(C12-Pad2)") (class "Default")
      (node (ref "C12") (pin "2") (pinfunction "2_2") (pintype "passive"))
      (node (ref "C13") (pin "2") (pinfunction "2_2") (pintype "passive"))
      (node (ref "C14") (pin "2") (pinfunction "2_2") (pintype "passive"))
    )
    (net (code "49") (name "Net-(D1-C)") (class "Default")
      (node (ref "D1") (pin "1") (pinfunction "C_1") (pintype "passive"))
      (node (ref "L1") (pin "1") (pinfunction "1_1") (pintype "passive"))
      (node (ref "U1") (pin "2") (pinfunction "Output_2") (pintype "output"))
    )
    (net (code "50") (name "Net-(GREEN1-K)") (class "Default")
      (node (ref "GREEN1") (pin "2") (pinfunction "K_2") (pintype "passive"))
      (node (ref "U6") (pin "14") (pinfunction "OUT3_14") (pintype "output"))
    )
    (net (code "51") (name "Net-(GREEN2-K)") (class "Default")
      (node (ref "GREEN2") (pin "2") (pinfunction "K_2") (pintype "passive"))
      (node (ref "U6") (pin "11") (pinfunction "OUT6_11") (pintype "output"))
    )
    (net (code "52") (name "Net-(Q1-C)") (class "Default")
      (node (ref "Digit11") (pin "3") (pinfunction "K_3") (pintype "passive"))
      (node (ref "Digit11") (pin "8") (pinfunction "K_8") (pintype "passive"))
      (node (ref "Q1") (pin "3") (pinfunction "C_3") (pintype "passive"))
    )
    (net (code "53") (name "Net-(Q2-C)") (class "Default")
      (node (ref "Digit12") (pin "3") (pinfunction "K_3") (pintype "passive"))
      (node (ref "Digit12") (pin "8") (pinfunction "K_8") (pintype "passive"))
      (node (ref "Q2") (pin "3") (pinfunction "C_3") (pintype "passive"))
    )
    (net (code "54") (name "Net-(Q3-C)") (class "Default")
      (node (ref "Digit21") (pin "3") (pinfunction "K_3") (pintype "passive"))
      (node (ref "Digit21") (pin "8") (pinfunction "K_8") (pintype "passive"))
      (node (ref "Q3") (pin "3") (pinfunction "C_3") (pintype "passive"))
    )
    (net (code "55") (name "Net-(Q4-C)") (class "Default")
      (node (ref "Digit22") (pin "3") (pinfunction "K_3") (pintype "passive"))
      (node (ref "Digit22") (pin "8") (pinfunction "K_8") (pintype "passive"))
      (node (ref "Q4") (pin "3") (pinfunction "C_3") (pintype "passive"))
    )
    (net (code "56") (name "Net-(RED1-K)") (class "Default")
      (node (ref "RED1") (pin "2") (pinfunction "K_2") (pintype "passive"))
      (node (ref "U6") (pin "16") (pinfunction "OUT1_16") (pintype "input"))
    )
    (net (code "57") (name "Net-(RED2-K)") (class "Default")
      (node (ref "RED2") (pin "2") (pinfunction "K_2") (pintype "passive"))
      (node (ref "U6") (pin "13") (pinfunction "OUT4_13") (pintype "output"))
    )
    (net (code "58") (name "Net-(U3-SDA)") (class "Default")
      (node (ref "R2") (pin "1") (pinfunction "1_1") (pintype "passive"))
      (node (ref "U3") (pin "15") (pinfunction "SDA_15") (pintype "bidirectional"))
    )
    (net (code "59") (name "Net-(U4-PB12)") (class "Default")
      (node (ref "R21") (pin "1") (pinfunction "1_1") (pintype "passive"))
      (node (ref "U4") (pin "25") (pinfunction "PB12_25") (pintype "bidirectional"))
    )
    (net (code "60") (name "Net-(U4-PB13)") (class "Default")
      (node (ref "R22") (pin "1") (pinfunction "1_1") (pintype "passive"))
      (node (ref "U4") (pin "26") (pinfunction "PB13_26") (pintype "bidirectional"))
    )
    (net (code "61") (name "Net-(U4-PB14)") (class "Default")
      (node (ref "R23") (pin "1") (pinfunction "1_1") (pintype "passive"))
      (node (ref "U4") (pin "27") (pinfunction "PB14_27") (pintype "bidirectional"))
    )
    (net (code "62") (name "Net-(U4-PB15)") (class "Default")
      (node (ref "R24") (pin "1") (pinfunction "1_1") (pintype "passive"))
      (node (ref "U4") (pin "28") (pinfunction "PB15_28") (pintype "bidirectional"))
    )
    (net (code "63") (name "Net-(U4-PC14-OSC32_IN)") (class "Default")
      (node (ref "C6") (pin "2") (pinfunction "2_2") (pintype "passive"))
      (node (ref "U4") (pin "3") (pinfunction "PC14-OSC32_IN_3") (pintype "bidirectional"))
      (node (ref "Y1") (pin "2") (pinfunction "2_2") (pintype "passive"))
    )
    (net (code "64") (name "Net-(U4-PC15-OSC32_OUT)") (class "Default")
      (node (ref "C7") (pin "2") (pinfunction "2_2") (pintype "passive"))
      (node (ref "U4") (pin "4") (pinfunction "PC15-OSC32_OUT_4") (pintype "bidirectional"))
      (node (ref "Y1") (pin "1") (pinfunction "1_1") (pintype "passive"))
    )
    (net (code "65") (name "Net-(U4-PH0-OSC_IN)") (class "Default")
      (node (ref "C8") (pin "2") (pinfunction "2_2") (pintype "passive"))
      (node (ref "U4") (pin "5") (pinfunction "PH0-OSC_IN_5") (pintype "bidirectional"))
      (node (ref "Y2") (pin "2") (pinfunction "2_2") (pintype "passive"))
    )
    (net (code "66") (name "Net-(U4-PH1-OSC_OUT)") (class "Default")
      (node (ref "C9") (pin "2") (pinfunction "2_2") (pintype "passive"))
      (node (ref "U4") (pin "6") (pinfunction "PH1-OSC_OUT_6") (pintype "bidirectional"))
      (node (ref "Y2") (pin "1") (pinfunction "1_1") (pintype "passive"))
    )
    (net (code "67") (name "Net-(U4-VCAP1)") (class "Default")
      (node (ref "C10") (pin "1") (pinfunction "1_1") (pintype "passive"))
      (node (ref "U4") (pin "22") (pinfunction "VCAP1_22") (pintype "passive"))
    )
    (net (code "68") (name "Net-(U5-B1)") (class "Default")
      (node (ref "R3") (pin "1") (pinfunction "1_1") (pintype "passive"))
      (node (ref "U5") (pin "18") (pinfunction "B1_18") (pintype "passive"))
    )
    (net (code "69") (name "Net-(U5-B2)") (class "Default")
      (node (ref "R4") (pin "1") (pinfunction "1_1") (pintype "passive"))
      (node (ref "U5") (pin "17") (pinfunction "B2_17") (pintype "passive"))
    )
    (net (code "70") (name "Net-(U5-B3)") (class "Default")
      (node (ref "R5") (pin "1") (pinfunction "1_1") (pintype "passive"))
      (node (ref "U5") (pin "16") (pinfunction "B3_16") (pintype "passive"))
    )
    (net (code "71") (name "Net-(U5-B4)") (class "Default")
      (node (ref "R6") (pin "1") (pinfunction "1_1") (pintype "passive"))
      (node (ref "U5") (pin "15") (pinfunction "B4_15") (pintype "passive"))
    )
    (net (code "72") (name "Net-(U5-B5)") (class "Default")
      (node (ref "R7") (pin "1") (pinfunction "1_1") (pintype "passive"))
      (node (ref "U5") (pin "14") (pinfunction "B5_14") (pintype "passive"))
    )
    (net (code "73") (name "Net-(U5-B6)") (class "Default")
      (node (ref "R8") (pin "1") (pinfunction "1_1") (pintype "passive"))
      (node (ref "U5") (pin "13") (pinfunction "B6_13") (pintype "passive"))
    )
    (net (code "74") (name "Net-(U5-B7)") (class "Default")
      (node (ref "R9") (pin "1") (pinfunction "1_1") (pintype "passive"))
      (node (ref "U5") (pin "12") (pinfunction "B7_12") (pintype "passive"))
    )
    (net (code "75") (name "Net-(U5-B8)") (class "Default")
      (node (ref "R10") (pin "1") (pinfunction "1_1") (pintype "passive"))
      (node (ref "U5") (pin "11") (pinfunction "B8_11") (pintype "passive"))
    )
    (net (code "76") (name "Net-(U6-OUT2)") (class "Default")
      (node (ref "U6") (pin "15") (pinfunction "OUT2_15") (pintype "output"))
      (node (ref "YELLOW1") (pin "2") (pinfunction "K_2") (pintype "passive"))
    )
    (net (code "77") (name "Net-(U6-OUT5)") (class "Default")
      (node (ref "U6") (pin "12") (pinfunction "OUT5_12") (pintype "output"))
      (node (ref "YELLOW2") (pin "2") (pinfunction "K_2") (pintype "passive"))
    )
    (net (code "78") (name "unconnected-(1-Pad3)") (class "Default")
      (node (ref "1") (pin "3") (pinfunction "3_3") (pintype "power_in"))
    )
    (net (code "79") (name "unconnected-(LCD 16x2-CONTRAST-PadP$3)") (class "Default")
      (node (ref "LCD 16x2") (pin "P$3") (pinfunction "CONTRAST_P$3") (pintype "bidirectional+no_connect"))
    )
    (net (code "80") (name "unconnected-(LCD 16x2-DB0-PadP$7)") (class "Default")
      (node (ref "LCD 16x2") (pin "P$7") (pinfunction "DB0_P$7") (pintype "bidirectional+no_connect"))
    )
    (net (code "81") (name "unconnected-(LCD 16x2-DB1-PadP$8)") (class "Default")
      (node (ref "LCD 16x2") (pin "P$8") (pinfunction "DB1_P$8") (pintype "bidirectional+no_connect"))
    )
    (net (code "82") (name "unconnected-(LCD 16x2-DB2-PadP$9)") (class "Default")
      (node (ref "LCD 16x2") (pin "P$9") (pinfunction "DB2_P$9") (pintype "bidirectional+no_connect"))
    )
    (net (code "83") (name "unconnected-(LCD 16x2-DB3-PadP$10)") (class "Default")
      (node (ref "LCD 16x2") (pin "P$10") (pinfunction "DB3_P$10") (pintype "bidirectional+no_connect"))
    )
    (net (code "84") (name "unconnected-(LCD 16x2-LED_A-PadP$15)") (class "Default")
      (node (ref "LCD 16x2") (pin "P$15") (pinfunction "LED_A_P$15") (pintype "bidirectional+no_connect"))
    )
    (net (code "85") (name "unconnected-(LCD 16x2-LED_C-PadP$16)") (class "Default")
      (node (ref "LCD 16x2") (pin "P$16") (pinfunction "LED_C_P$16") (pintype "bidirectional+no_connect"))
    )
    (net (code "86") (name "unconnected-(SW3-Pad1)") (class "Default")
      (node (ref "SW3") (pin "1") (pinfunction "1_1") (pintype "passive"))
    )
    (net (code "87") (name "unconnected-(SW3-Pad3)") (class "Default")
      (node (ref "SW3") (pin "3") (pinfunction "3_3") (pintype "passive"))
    )
    (net (code "88") (name "unconnected-(SW4-Pad1)") (class "Default")
      (node (ref "SW4") (pin "1") (pinfunction "1_1") (pintype "passive"))
    )
    (net (code "89") (name "unconnected-(SW4-Pad3)") (class "Default")
      (node (ref "SW4") (pin "3") (pinfunction "3_3") (pintype "passive"))
    )
    (net (code "90") (name "unconnected-(SW5-Pad1)") (class "Default")
      (node (ref "SW5") (pin "1") (pinfunction "1_1") (pintype "passive"))
    )
    (net (code "91") (name "unconnected-(SW5-Pad3)") (class "Default")
      (node (ref "SW5") (pin "3") (pinfunction "3_3") (pintype "passive"))
    )
    (net (code "92") (name "unconnected-(SW6-Pad1)") (class "Default")
      (node (ref "SW6") (pin "1") (pinfunction "1_1") (pintype "passive"))
    )
    (net (code "93") (name "unconnected-(SW6-Pad2)") (class "Default")
      (node (ref "SW6") (pin "2") (pinfunction "2_2") (pintype "passive"))
    )
    (net (code "94") (name "unconnected-(SW6-Pad3)") (class "Default")
      (node (ref "SW6") (pin "3") (pinfunction "3_3") (pintype "passive"))
    )
    (net (code "95") (name "unconnected-(SW7-Pad1)") (class "Default")
      (node (ref "SW7") (pin "1") (pinfunction "1_1") (pintype "passive"))
    )
    (net (code "96") (name "unconnected-(SW7-Pad3)") (class "Default")
      (node (ref "SW7") (pin "3") (pinfunction "3_3") (pintype "passive"))
    )
    (net (code "97") (name "unconnected-(SW8-Pad1)") (class "Default")
      (node (ref "SW8") (pin "1") (pinfunction "1_1") (pintype "passive"))
    )
    (net (code "98") (name "unconnected-(SW8-Pad3)") (class "Default")
      (node (ref "SW8") (pin "3") (pinfunction "3_3") (pintype "passive"))
    )
    (net (code "99") (name "unconnected-(SW9-Pad1)") (class "Default")
      (node (ref "SW9") (pin "1") (pinfunction "1_1") (pintype "passive"))
    )
    (net (code "100") (name "unconnected-(SW9-Pad3)") (class "Default")
      (node (ref "SW9") (pin "3") (pinfunction "3_3") (pintype "passive"))
    )
    (net (code "101") (name "unconnected-(SW10-Pad1)") (class "Default")
      (node (ref "SW10") (pin "1") (pinfunction "1_1") (pintype "passive"))
    )
    (net (code "102") (name "unconnected-(SW10-Pad2)") (class "Default")
      (node (ref "SW10") (pin "2") (pinfunction "2_2") (pintype "passive"))
    )
    (net (code "103") (name "unconnected-(SW10-Pad3)") (class "Default")
      (node (ref "SW10") (pin "3") (pinfunction "3_3") (pintype "passive"))
    )
    (net (code "104") (name "unconnected-(SW11-Pad1)") (class "Default")
      (node (ref "SW11") (pin "1") (pinfunction "1_1") (pintype "passive"))
    )
    (net (code "105") (name "unconnected-(SW11-Pad3)") (class "Default")
      (node (ref "SW11") (pin "3") (pinfunction "3_3") (pintype "passive"))
    )
    (net (code "106") (name "unconnected-(SW12-Pad1)") (class "Default")
      (node (ref "SW12") (pin "1") (pinfunction "1_1") (pintype "passive"))
    )
    (net (code "107") (name "unconnected-(SW12-Pad3)") (class "Default")
      (node (ref "SW12") (pin "3") (pinfunction "3_3") (pintype "passive"))
    )
    (net (code "108") (name "unconnected-(SW13-Pad1)") (class "Default")
      (node (ref "SW13") (pin "1") (pinfunction "1_1") (pintype "passive"))
    )
    (net (code "109") (name "unconnected-(SW13-Pad3)") (class "Default")
      (node (ref "SW13") (pin "3") (pinfunction "3_3") (pintype "passive"))
    )
    (net (code "110") (name "unconnected-(SW14-Pad1)") (class "Default")
      (node (ref "SW14") (pin "1") (pinfunction "1_1") (pintype "passive"))
    )
    (net (code "111") (name "unconnected-(SW14-Pad2)") (class "Default")
      (node (ref "SW14") (pin "2") (pinfunction "2_2") (pintype "passive"))
    )
    (net (code "112") (name "unconnected-(SW14-Pad3)") (class "Default")
      (node (ref "SW14") (pin "3") (pinfunction "3_3") (pintype "passive"))
    )
    (net (code "113") (name "unconnected-(SW15-Pad1)") (class "Default")
      (node (ref "SW15") (pin "1") (pinfunction "1_1") (pintype "passive"))
    )
    (net (code "114") (name "unconnected-(SW15-Pad3)") (class "Default")
      (node (ref "SW15") (pin "3") (pinfunction "3_3") (pintype "passive"))
    )
    (net (code "115") (name "unconnected-(SW16-Pad1)") (class "Default")
      (node (ref "SW16") (pin "1") (pinfunction "1_1") (pintype "passive"))
    )
    (net (code "116") (name "unconnected-(SW16-Pad3)") (class "Default")
      (node (ref "SW16") (pin "3") (pinfunction "3_3") (pintype "passive"))
    )
    (net (code "117") (name "unconnected-(SW17-Pad1)") (class "Default")
      (node (ref "SW17") (pin "1") (pinfunction "1_1") (pintype "passive"))
    )
    (net (code "118") (name "unconnected-(SW17-Pad3)") (class "Default")
      (node (ref "SW17") (pin "3") (pinfunction "3_3") (pintype "passive"))
    )
    (net (code "119") (name "unconnected-(SW18-Pad1)") (class "Default")
      (node (ref "SW18") (pin "1") (pinfunction "1_1") (pintype "passive"))
    )
    (net (code "120") (name "unconnected-(SW18-Pad3)") (class "Default")
      (node (ref "SW18") (pin "3") (pinfunction "3_3") (pintype "passive"))
    )
    (net (code "121") (name "unconnected-(U3-P3-Pad7)") (class "Default")
      (node (ref "U3") (pin "7") (pinfunction "P3_7") (pintype "bidirectional+no_connect"))
    )
    (net (code "122") (name "unconnected-(U3-~{INT}-Pad13)") (class "Default")
      (node (ref "U3") (pin "13") (pinfunction "~{INT}_13") (pintype "open_collector+no_connect"))
    )
    (net (code "123") (name "unconnected-(U4-EP-Pad49)") (class "Default")
      (node (ref "U4") (pin "49") (pinfunction "EP_49") (pintype "power_in+no_connect"))
    )
    (net (code "124") (name "unconnected-(U4-PB0-Pad18)") (class "Default")
      (node (ref "U4") (pin "18") (pinfunction "PB0_18") (pintype "bidirectional+no_connect"))
    )
    (net (code "125") (name "unconnected-(U4-PC13-ANTI_TAMP-Pad2)") (class "Default")
      (node (ref "U4") (pin "2") (pinfunction "PC13-ANTI_TAMP_2") (pintype "bidirectional+no_connect"))
    )
    (net (code "126") (name "unconnected-(U4-VBAT-Pad1)") (class "Default")
      (node (ref "U4") (pin "1") (pinfunction "VBAT_1") (pintype "power_in"))
    )
    (net (code "127") (name "unconnected-(U4-VREF+-Pad9)") (class "Default")
      (node (ref "U4") (pin "9") (pinfunction "VREF+_9") (pintype "power_in+no_connect"))
    )
    (net (code "128") (name "unconnected-(U6-IN7-Pad7)") (class "Default")
      (node (ref "U6") (pin "7") (pinfunction "IN7_7") (pintype "input+no_connect"))
    )
    (net (code "129") (name "unconnected-(U6-OUT7-Pad10)") (class "Default")
      (node (ref "U6") (pin "10") (pinfunction "OUT7_10") (pintype "output"))
    )
  )
)
